# bridge-pcb.net
KiCad netlist of a schematic drawn in EAGLE
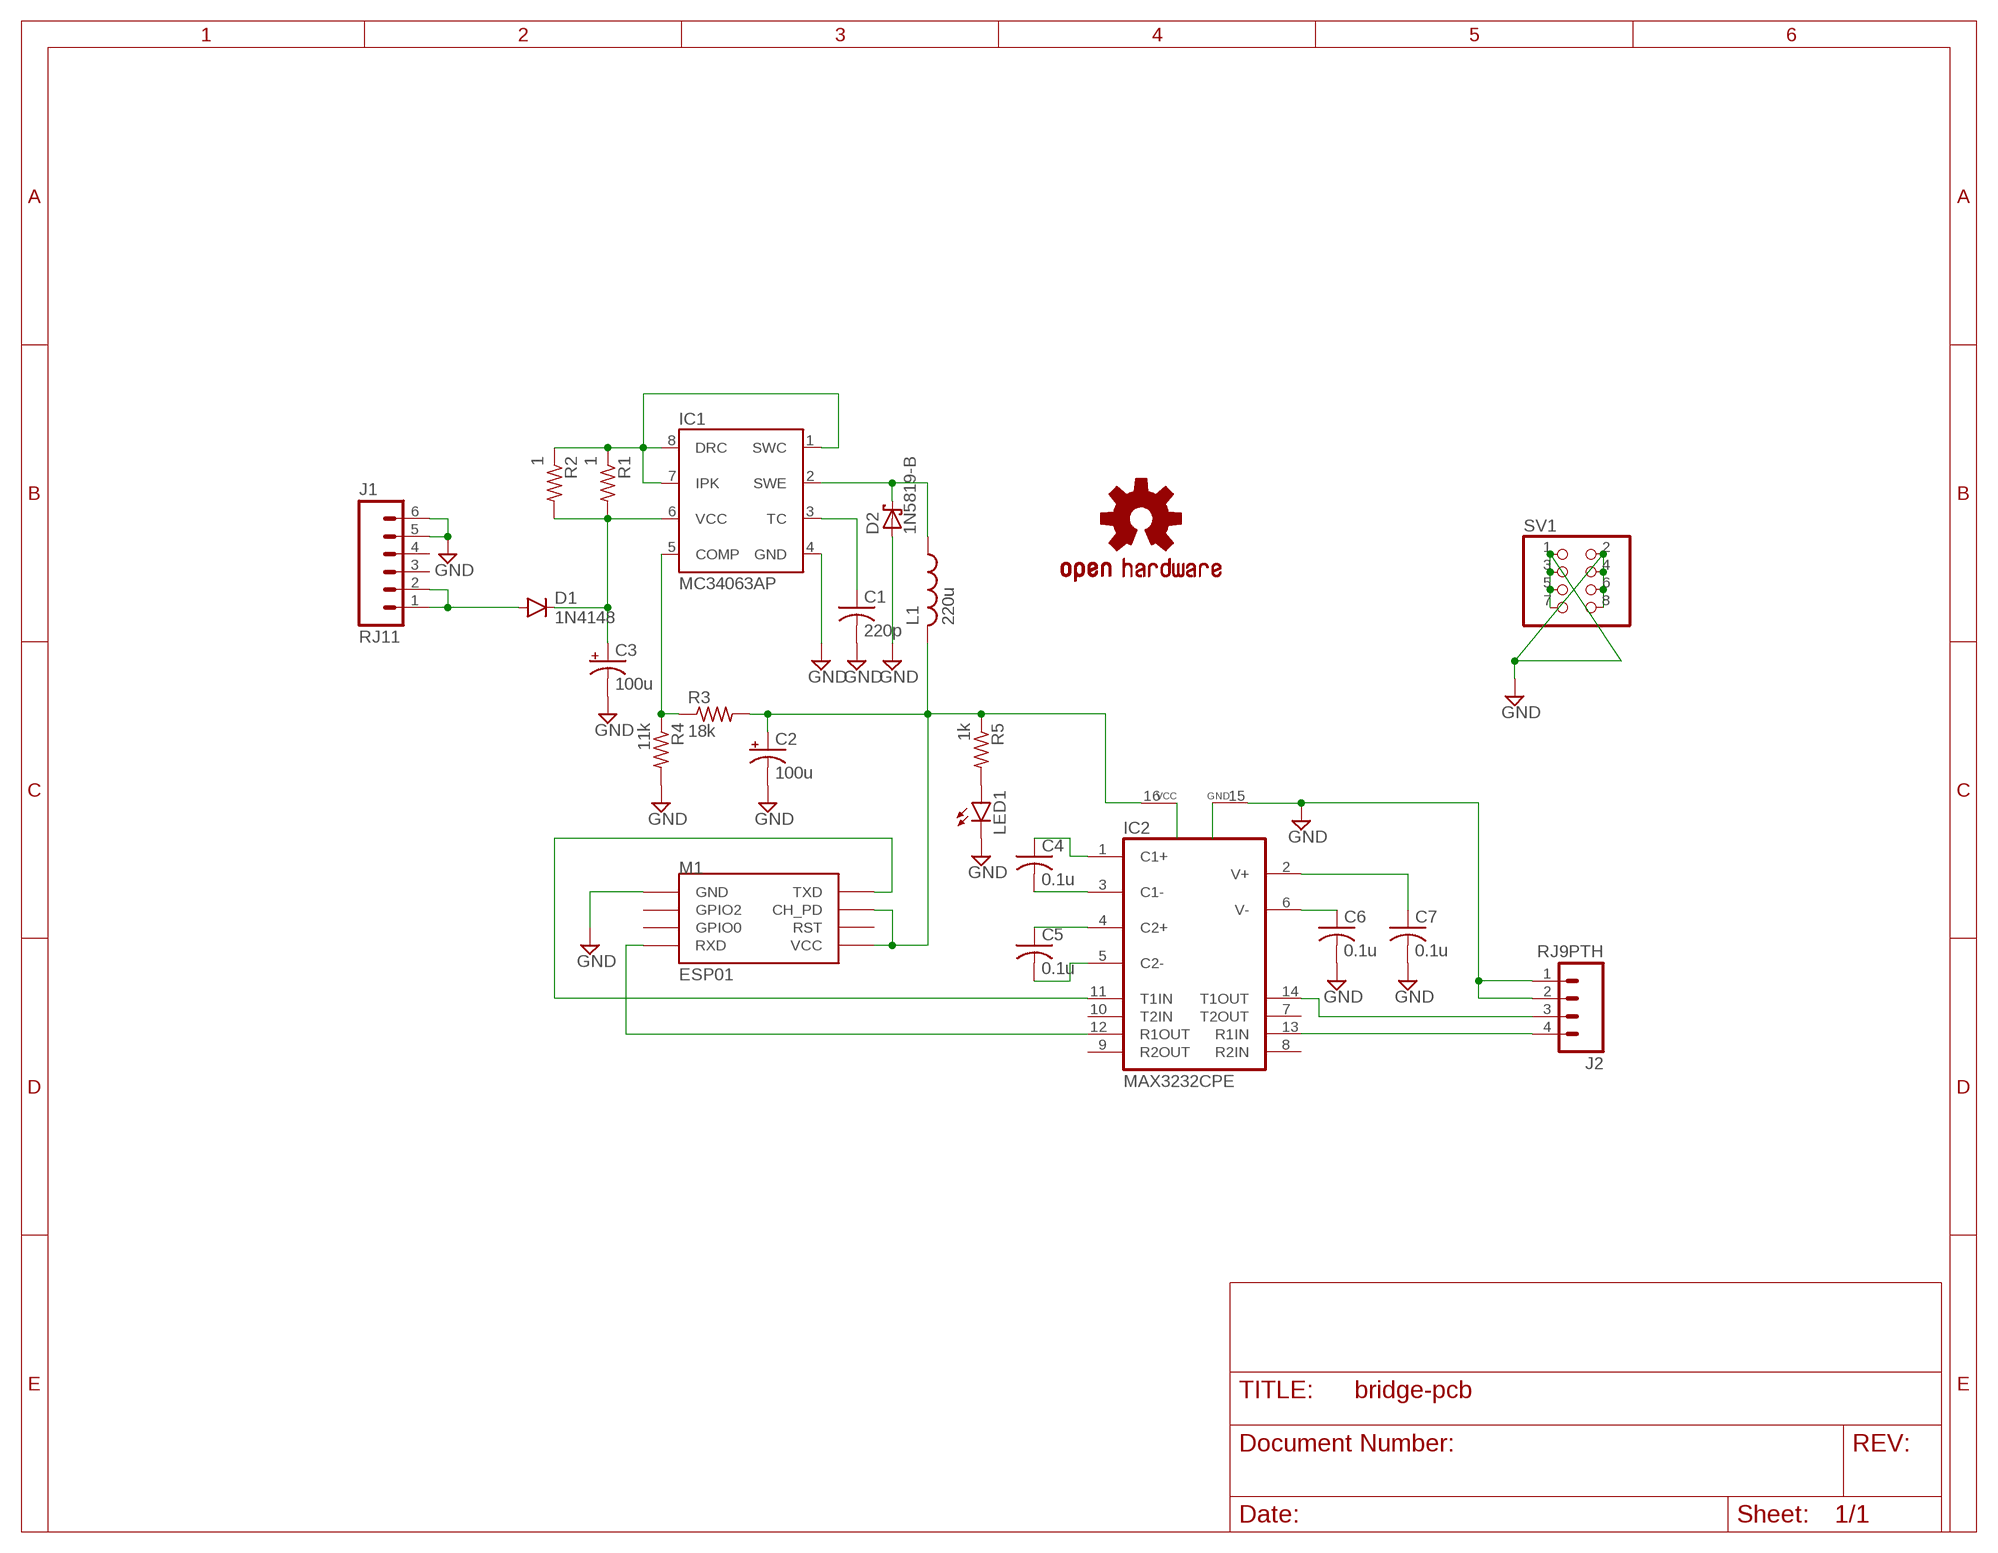
[diagram p0: schematic, sheet 1]

(export (version "E")
  (design (tool "Eeschema 10.0.6"))
  (components
    (comp (ref "C1")
      (value "220p")
      (footprint "eagle-import:C025-024X044")
      (libsource (lib "eagle-import") (part "C-US025-024X044"))
    )
    (comp (ref "C2")
      (value "100u")
      (footprint "eagle-import:E2,5-5")
      (libsource (lib "eagle-import") (part "CPOL-USE2.5-5"))
    )
    (comp (ref "C3")
      (value "100u")
      (footprint "eagle-import:E2,5-5")
      (libsource (lib "eagle-import") (part "CPOL-USE2.5-5"))
    )
    (comp (ref "C4")
      (value "0.1u")
      (footprint "eagle-import:C025-024X044")
      (libsource (lib "eagle-import") (part "C-US025-024X044"))
    )
    (comp (ref "C5")
      (value "0.1u")
      (footprint "eagle-import:C025-024X044")
      (libsource (lib "eagle-import") (part "C-US025-024X044"))
    )
    (comp (ref "C6")
      (value "0.1u")
      (footprint "eagle-import:C025-024X044")
      (libsource (lib "eagle-import") (part "C-US025-024X044"))
    )
    (comp (ref "C7")
      (value "0.1u")
      (footprint "eagle-import:C025-024X044")
      (libsource (lib "eagle-import") (part "C-US025-024X044"))
    )
    (comp (ref "D1")
      (value "1N4148")
      (footprint "eagle-import:DIODE-1N4148")
      (libsource (lib "eagle-import") (part "DIODE1N4148"))
    )
    (comp (ref "D2")
      (value "1N5819-B")
      (footprint "eagle-import:DO41-7.6")
      (libsource (lib "eagle-import") (part "1N5819-B"))
    )
    (comp (ref "IC1")
      (value "MC34063AP")
      (footprint "eagle-import:DIL-08")
      (libsource (lib "eagle-import") (part "MC34063AP"))
    )
    (comp (ref "IC2")
      (value "MAX3232CPE")
      (footprint "eagle-import:DIL16")
      (fields (field (name "MF") "MAXIM") (field (name "MPN") "MAX3232CPE+"))
      (libsource (lib "eagle-import") (part "MAX3232PEC"))
    )
    (comp (ref "J1")
      (value "RJ11")
      (footprint "eagle-import:RJ11-6")
      (libsource (lib "eagle-import") (part "RJ11-6PTH"))
    )
    (comp (ref "J2")
      (value "RJ9PTH")
      (footprint "eagle-import:RJ9")
      (libsource (lib "eagle-import") (part "RJ9PTH"))
    )
    (comp (ref "L1")
      (value "220u")
      (footprint "eagle-import:6000-XXXX-RC")
      (libsource (lib "eagle-import") (part "L-US6000-XXX-RC"))
    )
    (comp (ref "LED1")
      (value "LED5MM")
      (footprint "eagle-import:LED5MM")
      (libsource (lib "eagle-import") (part "LED5MM"))
    )
    (comp (ref "LOGO1")
      (value "OSHW-LOGOM")
      (footprint "eagle-import:OSHW-LOGO-M")
      (libsource (lib "eagle-import") (part "OSHW-LOGOM"))
    )
    (comp (ref "M1")
      (value "ESP01")
      (footprint "eagle-import:ESP01")
      (libsource (lib "eagle-import") (part "ESP01"))
    )
    (comp (ref "R1")
      (value "1")
      (footprint "eagle-import:0204V")
      (libsource (lib "eagle-import") (part "R-US_0204/2V"))
    )
    (comp (ref "R2")
      (value "1")
      (footprint "eagle-import:0204V")
      (libsource (lib "eagle-import") (part "R-US_0204/2V"))
    )
    (comp (ref "R3")
      (value "18k")
      (footprint "eagle-import:0204V")
      (libsource (lib "eagle-import") (part "R-US_0204/2V"))
    )
    (comp (ref "R4")
      (value "11k")
      (footprint "eagle-import:0204V")
      (libsource (lib "eagle-import") (part "R-US_0204/2V"))
    )
    (comp (ref "R5")
      (value "1k")
      (footprint "eagle-import:0204_7")
      (libsource (lib "eagle-import") (part "R-US_0204/7"))
    )
    (comp (ref "SV1")
      (value "PINHD-2X4")
      (footprint "eagle-import:2X04")
      (libsource (lib "eagle-import") (part "PINHD-2X4"))
    )
  )
  (nets
    (net (code "1") (name "GND") (class "Default")
      (node (ref "C1") (pin "2") (pinfunction "2_2") (pintype "passive"))
      (node (ref "C2") (pin "-") (pinfunction "-_-") (pintype "passive"))
      (node (ref "C3") (pin "-") (pinfunction "-_-") (pintype "passive"))
      (node (ref "C6") (pin "2") (pinfunction "2_2") (pintype "passive"))
      (node (ref "C7") (pin "2") (pinfunction "2_2") (pintype "passive"))
      (node (ref "D2") (pin "A") (pinfunction "A_A") (pintype "passive"))
      (node (ref "IC1") (pin "4") (pinfunction "GND_4") (pintype "power_in"))
      (node (ref "IC2") (pin "15") (pinfunction "GND_15") (pintype "power_in"))
      (node (ref "J1") (pin "5") (pinfunction "5_5") (pintype "passive"))
      (node (ref "J1") (pin "6") (pinfunction "6_6") (pintype "passive"))
      (node (ref "J2") (pin "1") (pinfunction "1_1") (pintype "passive"))
      (node (ref "J2") (pin "2") (pinfunction "2_2") (pintype "passive"))
      (node (ref "LED1") (pin "K") (pinfunction "C_K") (pintype "passive"))
      (node (ref "M1") (pin "GND") (pinfunction "GND_GND") (pintype "bidirectional"))
      (node (ref "R4") (pin "2") (pinfunction "2_2") (pintype "passive"))
      (node (ref "SV1") (pin "1") (pinfunction "1_1") (pintype "passive"))
      (node (ref "SV1") (pin "2") (pinfunction "2_2") (pintype "passive"))
      (node (ref "SV1") (pin "3") (pinfunction "3_3") (pintype "passive"))
      (node (ref "SV1") (pin "4") (pinfunction "4_4") (pintype "passive"))
      (node (ref "SV1") (pin "5") (pinfunction "5_5") (pintype "passive"))
      (node (ref "SV1") (pin "6") (pinfunction "6_6") (pintype "passive"))
      (node (ref "SV1") (pin "7") (pinfunction "7_7") (pintype "passive"))
      (node (ref "SV1") (pin "8") (pinfunction "8_8") (pintype "passive"))
    )
    (net (code "2") (name "Net-(D1-PadA)") (class "Default")
      (node (ref "D1") (pin "A") (pinfunction "A_A") (pintype "passive"))
      (node (ref "J1") (pin "1") (pinfunction "1_1") (pintype "passive"))
      (node (ref "J1") (pin "2") (pinfunction "2_2") (pintype "passive"))
    )
    (net (code "3") (name "Net-(IC1-COMP)") (class "Default")
      (node (ref "IC1") (pin "5") (pinfunction "COMP_5") (pintype "input"))
      (node (ref "R3") (pin "1") (pinfunction "1_1") (pintype "passive"))
      (node (ref "R4") (pin "1") (pinfunction "1_1") (pintype "passive"))
    )
    (net (code "4") (name "Net-(IC1-DRC)") (class "Default")
      (node (ref "IC1") (pin "1") (pinfunction "SWC_1") (pintype "bidirectional"))
      (node (ref "IC1") (pin "7") (pinfunction "IPK_7") (pintype "input"))
      (node (ref "IC1") (pin "8") (pinfunction "DRC_8") (pintype "input"))
      (node (ref "R1") (pin "1") (pinfunction "1_1") (pintype "passive"))
      (node (ref "R2") (pin "1") (pinfunction "1_1") (pintype "passive"))
    )
    (net (code "5") (name "Net-(IC1-SWE)") (class "Default")
      (node (ref "D2") (pin "C") (pinfunction "C_C") (pintype "passive"))
      (node (ref "IC1") (pin "2") (pinfunction "SWE_2") (pintype "bidirectional"))
      (node (ref "L1") (pin "1") (pinfunction "1_1") (pintype "passive"))
    )
    (net (code "6") (name "Net-(IC1-TC)") (class "Default")
      (node (ref "C1") (pin "1") (pinfunction "1_1") (pintype "passive"))
      (node (ref "IC1") (pin "3") (pinfunction "TC_3") (pintype "passive"))
    )
    (net (code "7") (name "Net-(IC1-VCC)") (class "Default")
      (node (ref "C3") (pin "+") (pinfunction "+_+") (pintype "passive"))
      (node (ref "D1") (pin "C") (pinfunction "C_C") (pintype "passive"))
      (node (ref "IC1") (pin "6") (pinfunction "VCC_6") (pintype "power_in"))
      (node (ref "R1") (pin "2") (pinfunction "2_2") (pintype "passive"))
      (node (ref "R2") (pin "2") (pinfunction "2_2") (pintype "passive"))
    )
    (net (code "8") (name "Net-(IC2A-C1+)") (class "Default")
      (node (ref "C4") (pin "1") (pinfunction "1_1") (pintype "passive"))
      (node (ref "IC2") (pin "1") (pinfunction "C1+_1") (pintype "bidirectional"))
    )
    (net (code "9") (name "Net-(IC2A-C1-)") (class "Default")
      (node (ref "C4") (pin "2") (pinfunction "2_2") (pintype "passive"))
      (node (ref "IC2") (pin "3") (pinfunction "C1-_3") (pintype "bidirectional"))
    )
    (net (code "10") (name "Net-(IC2A-C2+)") (class "Default")
      (node (ref "C5") (pin "1") (pinfunction "1_1") (pintype "passive"))
      (node (ref "IC2") (pin "4") (pinfunction "C2+_4") (pintype "bidirectional"))
    )
    (net (code "11") (name "Net-(IC2A-C2-)") (class "Default")
      (node (ref "C5") (pin "2") (pinfunction "2_2") (pintype "passive"))
      (node (ref "IC2") (pin "5") (pinfunction "C2-_5") (pintype "bidirectional"))
    )
    (net (code "12") (name "Net-(IC2A-R1IN)") (class "Default")
      (node (ref "IC2") (pin "13") (pinfunction "R1IN_13") (pintype "input"))
      (node (ref "J2") (pin "4") (pinfunction "4_4") (pintype "passive"))
    )
    (net (code "13") (name "Net-(IC2A-R1OUT)") (class "Default")
      (node (ref "IC2") (pin "12") (pinfunction "R1OUT_12") (pintype "output"))
      (node (ref "M1") (pin "RX") (pinfunction "RXD_RX") (pintype "bidirectional"))
    )
    (net (code "14") (name "Net-(IC2A-T1IN)") (class "Default")
      (node (ref "IC2") (pin "11") (pinfunction "T1IN_11") (pintype "input"))
      (node (ref "M1") (pin "TX") (pinfunction "TXD_TX") (pintype "bidirectional"))
    )
    (net (code "15") (name "Net-(IC2A-T1OUT)") (class "Default")
      (node (ref "IC2") (pin "14") (pinfunction "T1OUT_14") (pintype "output"))
      (node (ref "J2") (pin "3") (pinfunction "3_3") (pintype "passive"))
    )
    (net (code "16") (name "Net-(IC2A-V+)") (class "Default")
      (node (ref "C7") (pin "1") (pinfunction "1_1") (pintype "passive"))
      (node (ref "IC2") (pin "2") (pinfunction "V+_2") (pintype "bidirectional"))
    )
    (net (code "17") (name "Net-(IC2A-V-)") (class "Default")
      (node (ref "C6") (pin "1") (pinfunction "1_1") (pintype "passive"))
      (node (ref "IC2") (pin "6") (pinfunction "V-_6") (pintype "bidirectional"))
    )
    (net (code "18") (name "Net-(IC2B-VCC)") (class "Default")
      (node (ref "C2") (pin "+") (pinfunction "+_+") (pintype "passive"))
      (node (ref "IC2") (pin "16") (pinfunction "VCC_16") (pintype "power_in"))
      (node (ref "L1") (pin "2") (pinfunction "2_2") (pintype "passive"))
      (node (ref "M1") (pin "CH_PD") (pinfunction "CH_PD_CH_PD") (pintype "bidirectional"))
      (node (ref "M1") (pin "VCC") (pinfunction "VCC_VCC") (pintype "bidirectional"))
      (node (ref "R3") (pin "2") (pinfunction "2_2") (pintype "passive"))
      (node (ref "R5") (pin "1") (pinfunction "1_1") (pintype "passive"))
    )
    (net (code "19") (name "Net-(LED1-PadA)") (class "Default")
      (node (ref "LED1") (pin "A") (pinfunction "A_A") (pintype "passive"))
      (node (ref "R5") (pin "2") (pinfunction "2_2") (pintype "passive"))
    )
    (net (code "20") (name "unconnected-(IC2A-R2IN-Pad8)") (class "Default")
      (node (ref "IC2") (pin "8") (pinfunction "R2IN_8") (pintype "input"))
    )
    (net (code "21") (name "unconnected-(IC2A-R2OUT-Pad9)") (class "Default")
      (node (ref "IC2") (pin "9") (pinfunction "R2OUT_9") (pintype "output"))
    )
    (net (code "22") (name "unconnected-(IC2A-T2IN-Pad10)") (class "Default")
      (node (ref "IC2") (pin "10") (pinfunction "T2IN_10") (pintype "input"))
    )
    (net (code "23") (name "unconnected-(IC2A-T2OUT-Pad7)") (class "Default")
      (node (ref "IC2") (pin "7") (pinfunction "T2OUT_7") (pintype "output"))
    )
    (net (code "24") (name "unconnected-(J1-Pad3)") (class "Default")
      (node (ref "J1") (pin "3") (pinfunction "3_3") (pintype "passive"))
    )
    (net (code "25") (name "unconnected-(J1-Pad4)") (class "Default")
      (node (ref "J1") (pin "4") (pinfunction "4_4") (pintype "passive"))
    )
    (net (code "26") (name "unconnected-(M1-PadGPIO0)") (class "Default")
      (node (ref "M1") (pin "GPIO0") (pinfunction "GPIO0_GPIO0") (pintype "bidirectional"))
    )
    (net (code "27") (name "unconnected-(M1-PadGPIO2)") (class "Default")
      (node (ref "M1") (pin "GPIO2") (pinfunction "GPIO2_GPIO2") (pintype "bidirectional"))
    )
    (net (code "28") (name "unconnected-(M1-PadRST)") (class "Default")
      (node (ref "M1") (pin "RST") (pinfunction "RST_RST") (pintype "bidirectional"))
    )
  )
)
